# demeter_v21.net
KiCad netlist of a schematic drawn in EAGLE
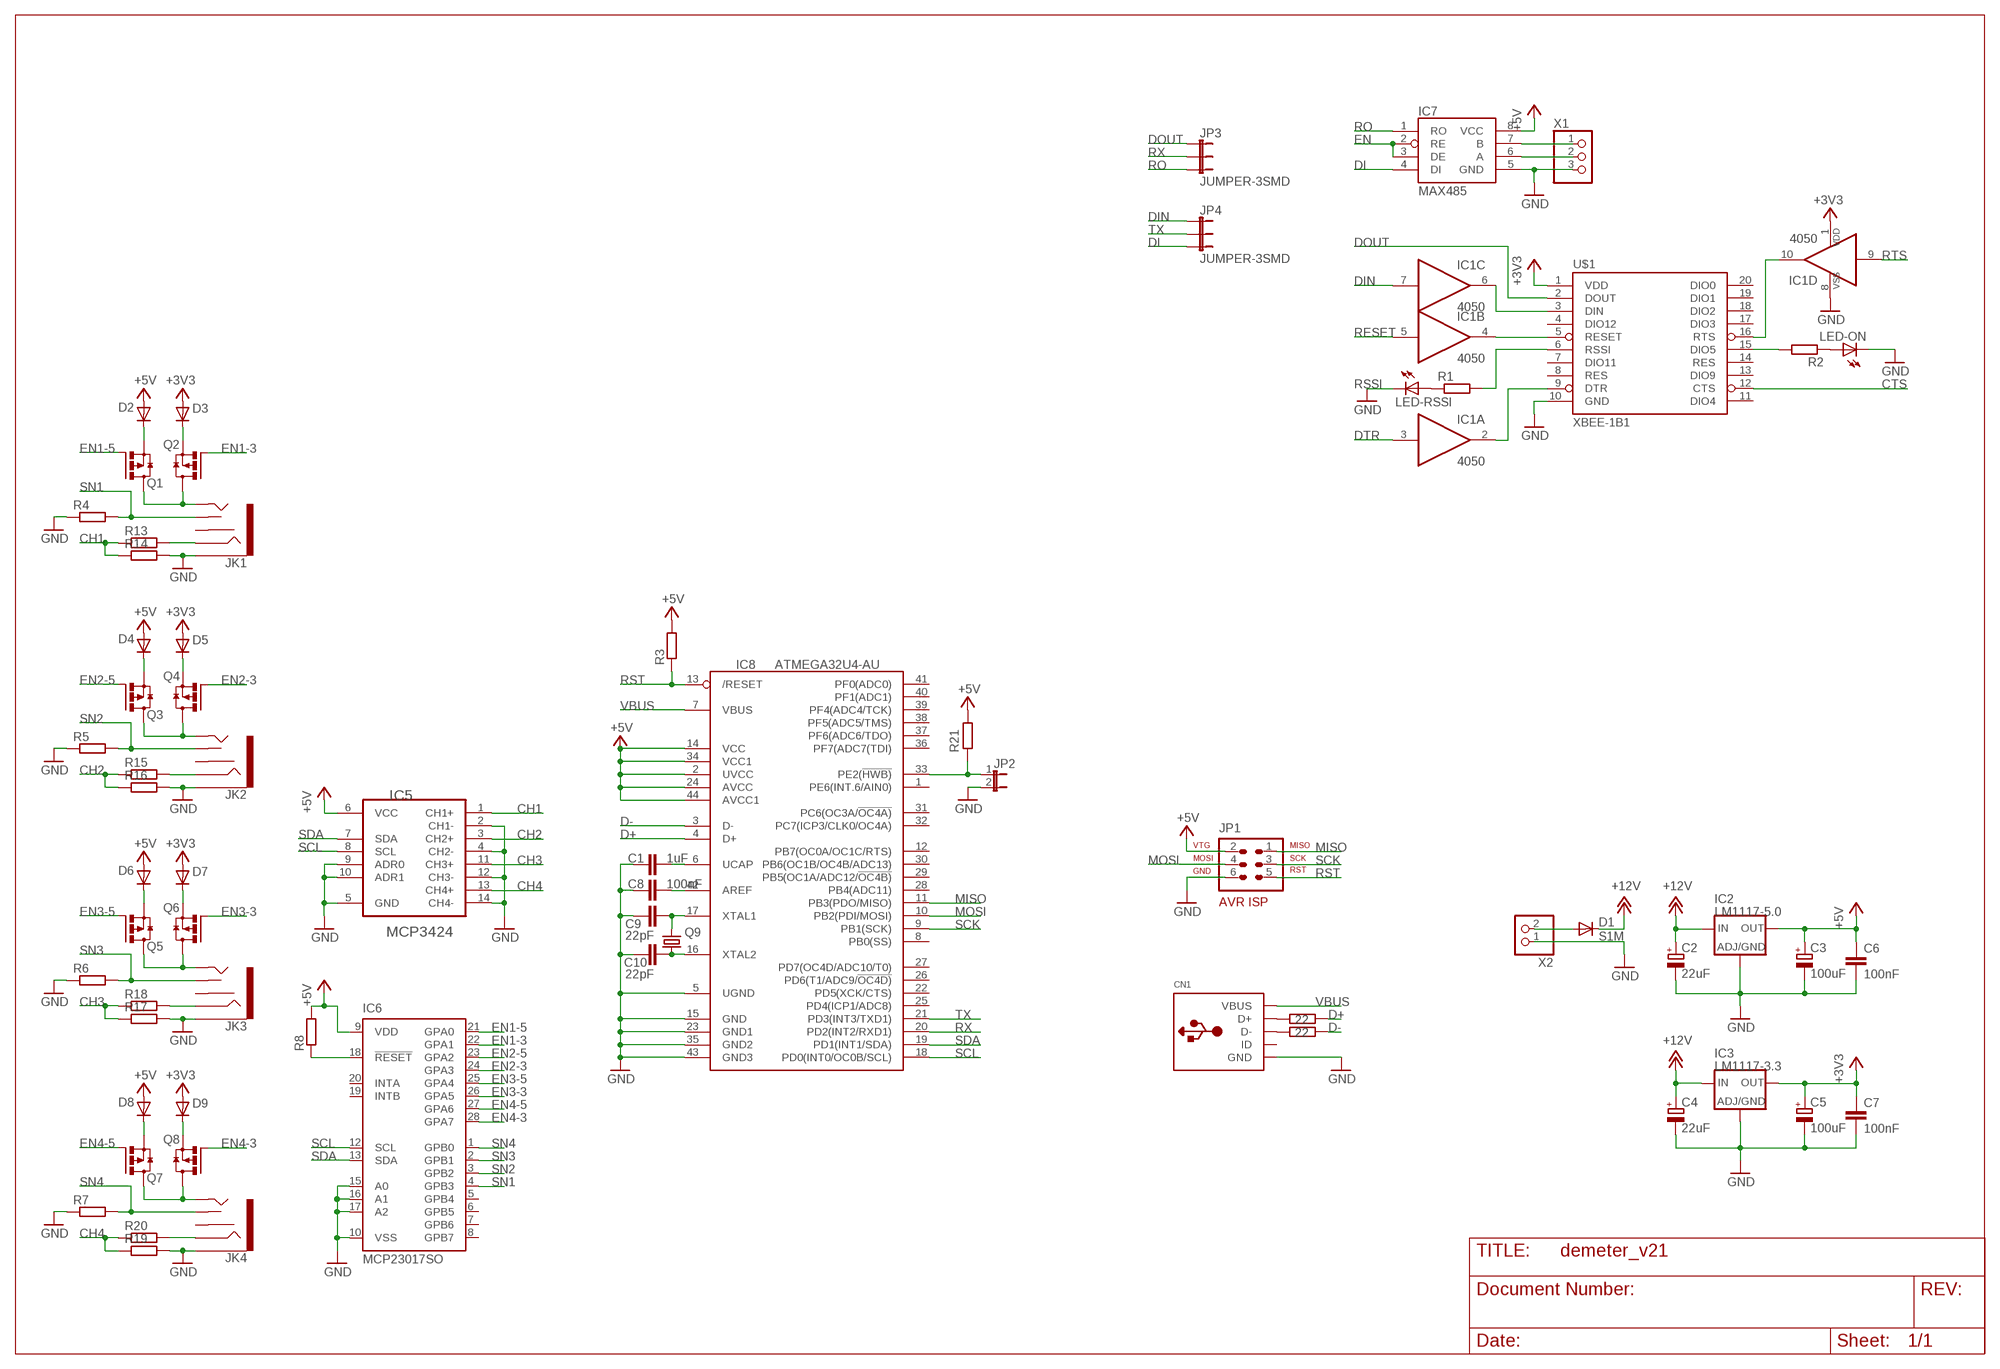
[diagram p0: schematic, sheet 1]

(export (version "E")
  (design (tool "Eeschema 10.0.6"))
  (components
    (comp (ref "C1")
      (value "1uF")
      (footprint "eagle-import:C0805K")
      (libsource (lib "eagle-import") (part "C-EUC0805K"))
    )
    (comp (ref "C2")
      (value "22uF")
      (footprint "eagle-import:PANASONIC_D")
      (libsource (lib "eagle-import") (part "CPOL-EUPD"))
    )
    (comp (ref "C3")
      (value "100uF")
      (footprint "eagle-import:PANASONIC_D")
      (libsource (lib "eagle-import") (part "CPOL-EUPD"))
    )
    (comp (ref "C4")
      (value "22uF")
      (footprint "eagle-import:PANASONIC_D")
      (libsource (lib "eagle-import") (part "CPOL-EUPD"))
    )
    (comp (ref "C5")
      (value "100uF")
      (footprint "eagle-import:PANASONIC_D")
      (libsource (lib "eagle-import") (part "CPOL-EUPD"))
    )
    (comp (ref "C6")
      (value "100nF")
      (footprint "eagle-import:C0805K")
      (libsource (lib "eagle-import") (part "C-EUC0805K"))
    )
    (comp (ref "C7")
      (value "100nF")
      (footprint "eagle-import:C0805K")
      (libsource (lib "eagle-import") (part "C-EUC0805K"))
    )
    (comp (ref "C8")
      (value "100nF")
      (footprint "eagle-import:C0805K")
      (libsource (lib "eagle-import") (part "C-EUC0805K"))
    )
    (comp (ref "C9")
      (value "22pF")
      (footprint "eagle-import:C0805K")
      (libsource (lib "eagle-import") (part "C-EUC0805K"))
    )
    (comp (ref "C10")
      (value "22pF")
      (footprint "eagle-import:C0805K")
      (libsource (lib "eagle-import") (part "C-EUC0805K"))
    )
    (comp (ref "CN1")
      (value "USBMINIB")
      (footprint "eagle-import:USB-MINIB")
      (libsource (lib "eagle-import") (part "USBMINIB"))
    )
    (comp (ref "D1")
      (value "S1M")
      (footprint "eagle-import:DO-214AC")
      (libsource (lib "eagle-import") (part "S1M"))
    )
    (comp (ref "D2")
      (value "MBR0520")
      (footprint "eagle-import:SOD123")
      (libsource (lib "eagle-import") (part "MBR0520"))
    )
    (comp (ref "D3")
      (value "MBR0520")
      (footprint "eagle-import:SOD123")
      (libsource (lib "eagle-import") (part "MBR0520"))
    )
    (comp (ref "D4")
      (value "MBR0520")
      (footprint "eagle-import:SOD123")
      (libsource (lib "eagle-import") (part "MBR0520"))
    )
    (comp (ref "D5")
      (value "MBR0520")
      (footprint "eagle-import:SOD123")
      (libsource (lib "eagle-import") (part "MBR0520"))
    )
    (comp (ref "D6")
      (value "MBR0520")
      (footprint "eagle-import:SOD123")
      (libsource (lib "eagle-import") (part "MBR0520"))
    )
    (comp (ref "D7")
      (value "MBR0520")
      (footprint "eagle-import:SOD123")
      (libsource (lib "eagle-import") (part "MBR0520"))
    )
    (comp (ref "D8")
      (value "MBR0520")
      (footprint "eagle-import:SOD123")
      (libsource (lib "eagle-import") (part "MBR0520"))
    )
    (comp (ref "D9")
      (value "MBR0520")
      (footprint "eagle-import:SOD123")
      (libsource (lib "eagle-import") (part "MBR0520"))
    )
    (comp (ref "IC1")
      (value "4050")
      (footprint "eagle-import:SO16")
      (libsource (lib "eagle-import") (part "4050D"))
    )
    (comp (ref "IC2")
      (value "LM1117-5.0")
      (footprint "eagle-import:DPACK")
      (libsource (lib "eagle-import") (part "LM1117DT"))
    )
    (comp (ref "IC3")
      (value "LM1117-3.3")
      (footprint "eagle-import:DPACK")
      (libsource (lib "eagle-import") (part "LM1117DT"))
    )
    (comp (ref "IC5")
      (value "MCP3424")
      (footprint "eagle-import:SO14")
      (fields (field (name "MPN") "MCP3424-E/SL"))
      (libsource (lib "eagle-import") (part "MCP3424"))
    )
    (comp (ref "IC6")
      (value "MCP23017SO")
      (footprint "eagle-import:SO28W")
      (fields (field (name "MF") "MICROCHIP") (field (name "MPN") "MCP23017-E/SO"))
      (libsource (lib "eagle-import") (part "MCP23017SO"))
    )
    (comp (ref "IC7")
      (value "MAX485")
      (footprint "eagle-import:SO08")
      (libsource (lib "eagle-import") (part "MAX485"))
    )
    (comp (ref "IC8")
      (value "ATMEGA32U4-AU")
      (footprint "eagle-import:TQFP44")
      (libsource (lib "eagle-import") (part "ATMEGA32U4-AU"))
    )
    (comp (ref "JK1")
      (value "AUDIO-JACK2PTH")
      (footprint "eagle-import:AUDIO-JACK")
      (libsource (lib "eagle-import") (part "AUDIO-JACK2PTH"))
    )
    (comp (ref "JK2")
      (value "AUDIO-JACK2PTH")
      (footprint "eagle-import:AUDIO-JACK")
      (libsource (lib "eagle-import") (part "AUDIO-JACK2PTH"))
    )
    (comp (ref "JK3")
      (value "AUDIO-JACK2PTH")
      (footprint "eagle-import:AUDIO-JACK")
      (libsource (lib "eagle-import") (part "AUDIO-JACK2PTH"))
    )
    (comp (ref "JK4")
      (value "AUDIO-JACK2PTH")
      (footprint "eagle-import:AUDIO-JACK")
      (libsource (lib "eagle-import") (part "AUDIO-JACK2PTH"))
    )
    (comp (ref "JP1")
      (value "AVR-ISP-6")
      (footprint "eagle-import:AVR-ISP-6")
      (libsource (lib "eagle-import") (part "AVR-ISP-6"))
    )
    (comp (ref "JP2")
      (value "JUMPER-2SMD-NO")
      (footprint "eagle-import:SJ_2S-NO")
      (libsource (lib "eagle-import") (part "JUMPER-2SMD-NO"))
    )
    (comp (ref "JP3")
      (value "JUMPER-3SMD")
      (footprint "eagle-import:SJ_3")
      (libsource (lib "eagle-import") (part "JUMPER-3SMD"))
    )
    (comp (ref "JP4")
      (value "JUMPER-3SMD")
      (footprint "eagle-import:SJ_3")
      (libsource (lib "eagle-import") (part "JUMPER-3SMD"))
    )
    (comp (ref "LED-ON")
      (value "LED3MM")
      (footprint "eagle-import:LED3MM")
      (libsource (lib "eagle-import") (part "LED3MM"))
    )
    (comp (ref "LED-RSSI")
      (value "LED3MM")
      (footprint "eagle-import:LED3MM")
      (libsource (lib "eagle-import") (part "LED3MM"))
    )
    (comp (ref "Q1")
      (value "IRLML6402")
      (footprint "eagle-import:SOT23")
      (libsource (lib "eagle-import") (part "IRLML6402"))
    )
    (comp (ref "Q2")
      (value "IRLML6402")
      (footprint "eagle-import:SOT23")
      (libsource (lib "eagle-import") (part "IRLML6402"))
    )
    (comp (ref "Q3")
      (value "IRLML6402")
      (footprint "eagle-import:SOT23")
      (libsource (lib "eagle-import") (part "IRLML6402"))
    )
    (comp (ref "Q4")
      (value "IRLML6402")
      (footprint "eagle-import:SOT23")
      (libsource (lib "eagle-import") (part "IRLML6402"))
    )
    (comp (ref "Q5")
      (value "IRLML6402")
      (footprint "eagle-import:SOT23")
      (libsource (lib "eagle-import") (part "IRLML6402"))
    )
    (comp (ref "Q6")
      (value "IRLML6402")
      (footprint "eagle-import:SOT23")
      (libsource (lib "eagle-import") (part "IRLML6402"))
    )
    (comp (ref "Q7")
      (value "IRLML6402")
      (footprint "eagle-import:SOT23")
      (libsource (lib "eagle-import") (part "IRLML6402"))
    )
    (comp (ref "Q8")
      (value "IRLML6402")
      (footprint "eagle-import:SOT23")
      (libsource (lib "eagle-import") (part "IRLML6402"))
    )
    (comp (ref "Q9")
      (value "CRYSTALHC49UP")
      (footprint "eagle-import:HC49UP")
      (libsource (lib "eagle-import") (part "CRYSTALHC49UP"))
    )
    (comp (ref "R1")
      (value "R-EU_R0805")
      (footprint "eagle-import:R0805")
      (libsource (lib "eagle-import") (part "R-EU_R0805"))
    )
    (comp (ref "R2")
      (value "R-EU_R0805")
      (footprint "eagle-import:R0805")
      (libsource (lib "eagle-import") (part "R-EU_R0805"))
    )
    (comp (ref "R3")
      (value "R-EU_R0805")
      (footprint "eagle-import:R0805")
      (libsource (lib "eagle-import") (part "R-EU_R0805"))
    )
    (comp (ref "R4")
      (value "R-EU_R0805")
      (footprint "eagle-import:R0805")
      (libsource (lib "eagle-import") (part "R-EU_R0805"))
    )
    (comp (ref "R5")
      (value "R-EU_R0805")
      (footprint "eagle-import:R0805")
      (libsource (lib "eagle-import") (part "R-EU_R0805"))
    )
    (comp (ref "R6")
      (value "R-EU_R0805")
      (footprint "eagle-import:R0805")
      (libsource (lib "eagle-import") (part "R-EU_R0805"))
    )
    (comp (ref "R7")
      (value "R-EU_R0805")
      (footprint "eagle-import:R0805")
      (libsource (lib "eagle-import") (part "R-EU_R0805"))
    )
    (comp (ref "R8")
      (value "R-EU_R0805")
      (footprint "eagle-import:R0805")
      (libsource (lib "eagle-import") (part "R-EU_R0805"))
    )
    (comp (ref "R9")
      (value "22")
      (footprint "eagle-import:R0805")
      (libsource (lib "eagle-import") (part "R-EU_R0805"))
    )
    (comp (ref "R10")
      (value "22")
      (footprint "eagle-import:R0805")
      (libsource (lib "eagle-import") (part "R-EU_R0805"))
    )
    (comp (ref "R13")
      (value "R-EU_R0805")
      (footprint "eagle-import:R0805")
      (libsource (lib "eagle-import") (part "R-EU_R0805"))
    )
    (comp (ref "R14")
      (value "R-EU_R0805")
      (footprint "eagle-import:R0805")
      (libsource (lib "eagle-import") (part "R-EU_R0805"))
    )
    (comp (ref "R15")
      (value "R-EU_R0805")
      (footprint "eagle-import:R0805")
      (libsource (lib "eagle-import") (part "R-EU_R0805"))
    )
    (comp (ref "R16")
      (value "R-EU_R0805")
      (footprint "eagle-import:R0805")
      (libsource (lib "eagle-import") (part "R-EU_R0805"))
    )
    (comp (ref "R17")
      (value "R-EU_R0805")
      (footprint "eagle-import:R0805")
      (libsource (lib "eagle-import") (part "R-EU_R0805"))
    )
    (comp (ref "R18")
      (value "R-EU_R0805")
      (footprint "eagle-import:R0805")
      (libsource (lib "eagle-import") (part "R-EU_R0805"))
    )
    (comp (ref "R19")
      (value "R-EU_R0805")
      (footprint "eagle-import:R0805")
      (libsource (lib "eagle-import") (part "R-EU_R0805"))
    )
    (comp (ref "R20")
      (value "R-EU_R0805")
      (footprint "eagle-import:R0805")
      (libsource (lib "eagle-import") (part "R-EU_R0805"))
    )
    (comp (ref "R21")
      (value "R-EU_R0805")
      (footprint "eagle-import:R0805")
      (libsource (lib "eagle-import") (part "R-EU_R0805"))
    )
    (comp (ref "U$1")
      (value "XBEE-1B1")
      (footprint "eagle-import:XBEE-1")
      (libsource (lib "eagle-import") (part "XBEE-1B1"))
    )
    (comp (ref "X1")
      (value "W237-103")
      (footprint "eagle-import:W237-103")
      (libsource (lib "eagle-import") (part "W237-103"))
    )
    (comp (ref "X2")
      (value "W237-102")
      (footprint "eagle-import:W237-102")
      (libsource (lib "eagle-import") (part "W237-102"))
    )
  )
  (nets
    (net (code "1") (name "+3V3") (class "Default")
      (node (ref "C5") (pin "+") (pinfunction "+_+") (pintype "passive"))
      (node (ref "C7") (pin "1") (pinfunction "1_1") (pintype "passive"))
      (node (ref "D3") (pin "A") (pinfunction "A_A") (pintype "passive"))
      (node (ref "D5") (pin "A") (pinfunction "A_A") (pintype "passive"))
      (node (ref "D7") (pin "A") (pinfunction "A_A") (pintype "passive"))
      (node (ref "D9") (pin "A") (pinfunction "A_A") (pintype "passive"))
      (node (ref "IC1") (pin "1") (pinfunction "VDD_1") (pintype "power_in"))
      (node (ref "IC3") (pin "4") (pinfunction "OUT_4") (pintype "passive"))
      (node (ref "U$1") (pin "1") (pinfunction "VDD_1") (pintype "power_in"))
    )
    (net (code "2") (name "+5V") (class "Default")
      (node (ref "C3") (pin "+") (pinfunction "+_+") (pintype "passive"))
      (node (ref "C6") (pin "1") (pinfunction "1_1") (pintype "passive"))
      (node (ref "D2") (pin "A") (pinfunction "A_A") (pintype "passive"))
      (node (ref "D4") (pin "A") (pinfunction "A_A") (pintype "passive"))
      (node (ref "D6") (pin "A") (pinfunction "A_A") (pintype "passive"))
      (node (ref "D8") (pin "A") (pinfunction "A_A") (pintype "passive"))
      (node (ref "IC2") (pin "4") (pinfunction "OUT_4") (pintype "passive"))
      (node (ref "IC5") (pin "6") (pinfunction "VCC_6") (pintype "power_in"))
      (node (ref "IC6") (pin "9") (pinfunction "VDD_9") (pintype "power_in"))
      (node (ref "IC7") (pin "8") (pinfunction "VCC_8") (pintype "bidirectional"))
      (node (ref "IC8") (pin "14") (pinfunction "VCC_14") (pintype "bidirectional"))
      (node (ref "IC8") (pin "2") (pinfunction "UVCC_2") (pintype "bidirectional"))
      (node (ref "IC8") (pin "24") (pinfunction "AVCC_24") (pintype "bidirectional"))
      (node (ref "IC8") (pin "34") (pinfunction "VCC1_34") (pintype "bidirectional"))
      (node (ref "IC8") (pin "44") (pinfunction "AVCC1_44") (pintype "bidirectional"))
      (node (ref "JP1") (pin "2") (pinfunction "VTG_2") (pintype "passive"))
      (node (ref "R21") (pin "1") (pinfunction "1_1") (pintype "passive"))
      (node (ref "R3") (pin "2") (pinfunction "2_2") (pintype "passive"))
      (node (ref "R8") (pin "2") (pinfunction "2_2") (pintype "passive"))
    )
    (net (code "3") (name "+12V") (class "Default")
      (node (ref "C2") (pin "+") (pinfunction "+_+") (pintype "passive"))
      (node (ref "C4") (pin "+") (pinfunction "+_+") (pintype "passive"))
      (node (ref "D1") (pin "C") (pinfunction "C_C") (pintype "passive"))
      (node (ref "IC2") (pin "3") (pinfunction "IN_3") (pintype "input"))
      (node (ref "IC3") (pin "3") (pinfunction "IN_3") (pintype "input"))
    )
    (net (code "4") (name "/CH1") (class "Default")
      (node (ref "IC5") (pin "1") (pinfunction "CH1+_1") (pintype "input"))
      (node (ref "R13") (pin "1") (pinfunction "1_1") (pintype "passive"))
      (node (ref "R14") (pin "1") (pinfunction "1_1") (pintype "passive"))
    )
    (net (code "5") (name "/CH2") (class "Default")
      (node (ref "IC5") (pin "3") (pinfunction "CH2+_3") (pintype "input"))
      (node (ref "R15") (pin "1") (pinfunction "1_1") (pintype "passive"))
      (node (ref "R16") (pin "1") (pinfunction "1_1") (pintype "passive"))
    )
    (net (code "6") (name "/CH3") (class "Default")
      (node (ref "IC5") (pin "11") (pinfunction "CH3+_11") (pintype "input"))
      (node (ref "R17") (pin "1") (pinfunction "1_1") (pintype "passive"))
      (node (ref "R18") (pin "1") (pinfunction "1_1") (pintype "passive"))
    )
    (net (code "7") (name "/CH4") (class "Default")
      (node (ref "IC5") (pin "13") (pinfunction "CH4+_13") (pintype "input"))
      (node (ref "R19") (pin "1") (pinfunction "1_1") (pintype "passive"))
      (node (ref "R20") (pin "1") (pinfunction "1_1") (pintype "passive"))
    )
    (net (code "8") (name "/CTS") (class "Default")
      (node (ref "U$1") (pin "12") (pinfunction "CTS_12") (pintype "output"))
    )
    (net (code "9") (name "/D+") (class "Default")
      (node (ref "IC8") (pin "4") (pinfunction "D+_4") (pintype "bidirectional"))
      (node (ref "R9") (pin "1") (pinfunction "1_1") (pintype "passive"))
    )
    (net (code "10") (name "/D-") (class "Default")
      (node (ref "IC8") (pin "3") (pinfunction "D-_3") (pintype "bidirectional"))
      (node (ref "R10") (pin "1") (pinfunction "1_1") (pintype "passive"))
    )
    (net (code "11") (name "/DI") (class "Default")
      (node (ref "IC7") (pin "4") (pinfunction "DI_4") (pintype "bidirectional"))
      (node (ref "JP4") (pin "3") (pinfunction "3_3") (pintype "passive"))
    )
    (net (code "12") (name "/DIN") (class "Default")
      (node (ref "IC1") (pin "7") (pinfunction "I_7") (pintype "input"))
      (node (ref "JP4") (pin "1") (pinfunction "1_1") (pintype "passive"))
    )
    (net (code "13") (name "/DOUT") (class "Default")
      (node (ref "JP3") (pin "1") (pinfunction "1_1") (pintype "passive"))
      (node (ref "U$1") (pin "2") (pinfunction "DOUT_2") (pintype "output"))
    )
    (net (code "14") (name "/DTR") (class "Default")
      (node (ref "IC1") (pin "3") (pinfunction "I_3") (pintype "input"))
    )
    (net (code "15") (name "/EN") (class "Default")
      (node (ref "IC7") (pin "2") (pinfunction "RE_2") (pintype "bidirectional"))
      (node (ref "IC7") (pin "3") (pinfunction "DE_3") (pintype "bidirectional"))
    )
    (net (code "16") (name "/EN1-3") (class "Default")
      (node (ref "IC6") (pin "22") (pinfunction "GPA1_22") (pintype "bidirectional"))
      (node (ref "Q2") (pin "1") (pinfunction "G_1") (pintype "passive"))
    )
    (net (code "17") (name "/EN1-5") (class "Default")
      (node (ref "IC6") (pin "21") (pinfunction "GPA0_21") (pintype "bidirectional"))
      (node (ref "Q1") (pin "1") (pinfunction "G_1") (pintype "passive"))
    )
    (net (code "18") (name "/EN2-3") (class "Default")
      (node (ref "IC6") (pin "24") (pinfunction "GPA3_24") (pintype "bidirectional"))
      (node (ref "Q4") (pin "1") (pinfunction "G_1") (pintype "passive"))
    )
    (net (code "19") (name "/EN2-5") (class "Default")
      (node (ref "IC6") (pin "23") (pinfunction "GPA2_23") (pintype "bidirectional"))
      (node (ref "Q3") (pin "1") (pinfunction "G_1") (pintype "passive"))
    )
    (net (code "20") (name "/EN3-3") (class "Default")
      (node (ref "IC6") (pin "26") (pinfunction "GPA5_26") (pintype "bidirectional"))
      (node (ref "Q6") (pin "1") (pinfunction "G_1") (pintype "passive"))
    )
    (net (code "21") (name "/EN3-5") (class "Default")
      (node (ref "IC6") (pin "25") (pinfunction "GPA4_25") (pintype "bidirectional"))
      (node (ref "Q5") (pin "1") (pinfunction "G_1") (pintype "passive"))
    )
    (net (code "22") (name "/EN4-3") (class "Default")
      (node (ref "IC6") (pin "28") (pinfunction "GPA7_28") (pintype "bidirectional"))
      (node (ref "Q8") (pin "1") (pinfunction "G_1") (pintype "passive"))
    )
    (net (code "23") (name "/EN4-5") (class "Default")
      (node (ref "IC6") (pin "27") (pinfunction "GPA6_27") (pintype "bidirectional"))
      (node (ref "Q7") (pin "1") (pinfunction "G_1") (pintype "passive"))
    )
    (net (code "24") (name "/MISO") (class "Default")
      (node (ref "IC8") (pin "11") (pinfunction "PB3(PDO/MISO)_11") (pintype "bidirectional"))
      (node (ref "JP1") (pin "1") (pinfunction "MISO_1") (pintype "passive"))
    )
    (net (code "25") (name "/MOSI") (class "Default")
      (node (ref "IC8") (pin "10") (pinfunction "PB2(PDI/MOSI)_10") (pintype "bidirectional"))
      (node (ref "JP1") (pin "4") (pinfunction "MOSI_4") (pintype "passive"))
    )
    (net (code "26") (name "/RESET") (class "Default")
      (node (ref "IC1") (pin "5") (pinfunction "I_5") (pintype "input"))
    )
    (net (code "27") (name "/RO") (class "Default")
      (node (ref "IC7") (pin "1") (pinfunction "RO_1") (pintype "bidirectional"))
      (node (ref "JP3") (pin "3") (pinfunction "3_3") (pintype "passive"))
    )
    (net (code "28") (name "/RSSI") (class "Default")
      (node (ref "R1") (pin "2") (pinfunction "2_2") (pintype "passive"))
      (node (ref "U$1") (pin "6") (pinfunction "RSSI_6") (pintype "bidirectional"))
    )
    (net (code "29") (name "/RST") (class "Default")
      (node (ref "IC8") (pin "13") (pinfunction "/RESET_13") (pintype "bidirectional"))
      (node (ref "JP1") (pin "5") (pinfunction "RST_5") (pintype "passive"))
      (node (ref "R3") (pin "1") (pinfunction "1_1") (pintype "passive"))
    )
    (net (code "30") (name "/RTS") (class "Default")
      (node (ref "IC1") (pin "9") (pinfunction "I_9") (pintype "input"))
    )
    (net (code "31") (name "/RX") (class "Default")
      (node (ref "IC8") (pin "20") (pinfunction "PD2(INT2/RXD1)_20") (pintype "bidirectional"))
      (node (ref "JP3") (pin "2") (pinfunction "2_2") (pintype "passive"))
    )
    (net (code "32") (name "/SCK") (class "Default")
      (node (ref "IC8") (pin "9") (pinfunction "PB1(SCK)_9") (pintype "bidirectional"))
      (node (ref "JP1") (pin "3") (pinfunction "SCK_3") (pintype "passive"))
    )
    (net (code "33") (name "/SCL") (class "Default")
      (node (ref "IC5") (pin "8") (pinfunction "SCL_8") (pintype "input"))
      (node (ref "IC6") (pin "12") (pinfunction "SCL_12") (pintype "input"))
      (node (ref "IC8") (pin "18") (pinfunction "PD0(INT0/OC0B/SCL)_18") (pintype "bidirectional"))
    )
    (net (code "34") (name "/SDA") (class "Default")
      (node (ref "IC5") (pin "7") (pinfunction "SDA_7") (pintype "bidirectional"))
      (node (ref "IC6") (pin "13") (pinfunction "SDA_13") (pintype "bidirectional"))
      (node (ref "IC8") (pin "19") (pinfunction "PD1(INT1/SDA)_19") (pintype "bidirectional"))
    )
    (net (code "35") (name "/SN1") (class "Default")
      (node (ref "IC6") (pin "4") (pinfunction "GPB3_4") (pintype "bidirectional"))
      (node (ref "JK1") (pin "TSH") (pinfunction "TSH_TSH") (pintype "bidirectional"))
      (node (ref "R4") (pin "2") (pinfunction "2_2") (pintype "passive"))
    )
    (net (code "36") (name "/SN2") (class "Default")
      (node (ref "IC6") (pin "3") (pinfunction "GPB2_3") (pintype "bidirectional"))
      (node (ref "JK2") (pin "TSH") (pinfunction "TSH_TSH") (pintype "bidirectional"))
      (node (ref "R5") (pin "2") (pinfunction "2_2") (pintype "passive"))
    )
    (net (code "37") (name "/SN3") (class "Default")
      (node (ref "IC6") (pin "2") (pinfunction "GPB1_2") (pintype "bidirectional"))
      (node (ref "JK3") (pin "TSH") (pinfunction "TSH_TSH") (pintype "bidirectional"))
      (node (ref "R6") (pin "2") (pinfunction "2_2") (pintype "passive"))
    )
    (net (code "38") (name "/SN4") (class "Default")
      (node (ref "IC6") (pin "1") (pinfunction "GPB0_1") (pintype "bidirectional"))
      (node (ref "JK4") (pin "TSH") (pinfunction "TSH_TSH") (pintype "bidirectional"))
      (node (ref "R7") (pin "2") (pinfunction "2_2") (pintype "passive"))
    )
    (net (code "39") (name "/TX") (class "Default")
      (node (ref "IC8") (pin "21") (pinfunction "PD3(INT3/TXD1)_21") (pintype "bidirectional"))
      (node (ref "JP4") (pin "2") (pinfunction "2_2") (pintype "passive"))
    )
    (net (code "40") (name "/VBUS") (class "Default")
      (node (ref "CN1") (pin "VBUS") (pinfunction "VBUS_VBUS") (pintype "power_in"))
      (node (ref "IC8") (pin "7") (pinfunction "VBUS_7") (pintype "bidirectional"))
    )
    (net (code "41") (name "GND") (class "Default")
      (node (ref "C1") (pin "2") (pinfunction "2_2") (pintype "passive"))
      (node (ref "C10") (pin "2") (pinfunction "2_2") (pintype "passive"))
      (node (ref "C2") (pin "-") (pinfunction "-_-") (pintype "passive"))
      (node (ref "C3") (pin "-") (pinfunction "-_-") (pintype "passive"))
      (node (ref "C4") (pin "-") (pinfunction "-_-") (pintype "passive"))
      (node (ref "C5") (pin "-") (pinfunction "-_-") (pintype "passive"))
      (node (ref "C6") (pin "2") (pinfunction "2_2") (pintype "passive"))
      (node (ref "C7") (pin "2") (pinfunction "2_2") (pintype "passive"))
      (node (ref "C8") (pin "2") (pinfunction "2_2") (pintype "passive"))
      (node (ref "C9") (pin "2") (pinfunction "2_2") (pintype "passive"))
      (node (ref "CN1") (pin "GND") (pinfunction "GND_GND") (pintype "power_in"))
      (node (ref "IC1") (pin "8") (pinfunction "VSS_8") (pintype "power_in"))
      (node (ref "IC2") (pin "1") (pinfunction "ADJ_1") (pintype "input"))
      (node (ref "IC3") (pin "1") (pinfunction "ADJ_1") (pintype "input"))
      (node (ref "IC5") (pin "10") (pinfunction "ADR1_10") (pintype "input"))
      (node (ref "IC5") (pin "12") (pinfunction "CH3-_12") (pintype "input"))
      (node (ref "IC5") (pin "14") (pinfunction "CH4-_14") (pintype "input"))
      (node (ref "IC5") (pin "2") (pinfunction "CH1-_2") (pintype "input"))
      (node (ref "IC5") (pin "4") (pinfunction "CH2-_4") (pintype "input"))
      (node (ref "IC5") (pin "5") (pinfunction "GND_5") (pintype "power_in"))
      (node (ref "IC5") (pin "9") (pinfunction "ADR0_9") (pintype "input"))
      (node (ref "IC6") (pin "10") (pinfunction "VSS_10") (pintype "power_in"))
      (node (ref "IC6") (pin "15") (pinfunction "A0_15") (pintype "input"))
      (node (ref "IC6") (pin "16") (pinfunction "A1_16") (pintype "input"))
      (node (ref "IC6") (pin "17") (pinfunction "A2_17") (pintype "input"))
      (node (ref "IC7") (pin "5") (pinfunction "GND_5") (pintype "bidirectional"))
      (node (ref "IC8") (pin "15") (pinfunction "GND_15") (pintype "bidirectional"))
      (node (ref "IC8") (pin "23") (pinfunction "GND1_23") (pintype "bidirectional"))
      (node (ref "IC8") (pin "35") (pinfunction "GND2_35") (pintype "bidirectional"))
      (node (ref "IC8") (pin "43") (pinfunction "GND3_43") (pintype "bidirectional"))
      (node (ref "IC8") (pin "5") (pinfunction "UGND_5") (pintype "bidirectional"))
      (node (ref "JK1") (pin "SLEEVE") (pinfunction "SLEEVE_SLEEVE") (pintype "bidirectional"))
      (node (ref "JK2") (pin "SLEEVE") (pinfunction "SLEEVE_SLEEVE") (pintype "bidirectional"))
      (node (ref "JK3") (pin "SLEEVE") (pinfunction "SLEEVE_SLEEVE") (pintype "bidirectional"))
      (node (ref "JK4") (pin "SLEEVE") (pinfunction "SLEEVE_SLEEVE") (pintype "bidirectional"))
      (node (ref "JP1") (pin "6") (pinfunction "GND_6") (pintype "passive"))
      (node (ref "JP2") (pin "2") (pinfunction "2_2") (pintype "passive"))
      (node (ref "LED-ON") (pin "K") (pinfunction "C_K") (pintype "passive"))
      (node (ref "LED-RSSI") (pin "K") (pinfunction "C_K") (pintype "passive"))
      (node (ref "R14") (pin "2") (pinfunction "2_2") (pintype "passive"))
      (node (ref "R16") (pin "2") (pinfunction "2_2") (pintype "passive"))
      (node (ref "R17") (pin "2") (pinfunction "2_2") (pintype "passive"))
      (node (ref "R19") (pin "2") (pinfunction "2_2") (pintype "passive"))
      (node (ref "R4") (pin "1") (pinfunction "1_1") (pintype "passive"))
      (node (ref "R5") (pin "1") (pinfunction "1_1") (pintype "passive"))
      (node (ref "R6") (pin "1") (pinfunction "1_1") (pintype "passive"))
      (node (ref "R7") (pin "1") (pinfunction "1_1") (pintype "passive"))
      (node (ref "U$1") (pin "10") (pinfunction "GND_10") (pintype "power_in"))
      (node (ref "X1") (pin "3") (pinfunction "3_3") (pintype "passive"))
      (node (ref "X2") (pin "1") (pinfunction "1_1") (pintype "passive"))
    )
    (net (code "42") (name "Net-(CN1-PadD+)") (class "Default")
      (node (ref "CN1") (pin "D+") (pinfunction "D+_D+") (pintype "bidirectional"))
      (node (ref "R9") (pin "2") (pinfunction "2_2") (pintype "passive"))
    )
    (net (code "43") (name "Net-(CN1-PadD-)") (class "Default")
      (node (ref "CN1") (pin "D-") (pinfunction "D-_D-") (pintype "bidirectional"))
      (node (ref "R10") (pin "2") (pinfunction "2_2") (pintype "passive"))
    )
    (net (code "44") (name "Net-(D1-PadA)") (class "Default")
      (node (ref "D1") (pin "A") (pinfunction "A_A") (pintype "passive"))
      (node (ref "X2") (pin "2") (pinfunction "2_2") (pintype "passive"))
    )
    (net (code "45") (name "Net-(IC1A-O)") (class "Default")
      (node (ref "IC1") (pin "2") (pinfunction "O_2") (pintype "output"))
      (node (ref "U$1") (pin "9") (pinfunction "DTR_9") (pintype "bidirectional"))
    )
    (net (code "46") (name "Net-(IC1B-O)") (class "Default")
      (node (ref "IC1") (pin "4") (pinfunction "O_4") (pintype "output"))
      (node (ref "U$1") (pin "5") (pinfunction "RESET_5") (pintype "input"))
    )
    (net (code "47") (name "Net-(IC1C-O)") (class "Default")
      (node (ref "IC1") (pin "6") (pinfunction "O_6") (pintype "output"))
      (node (ref "U$1") (pin "3") (pinfunction "DIN_3") (pintype "input"))
    )
    (net (code "48") (name "Net-(IC1D-O)") (class "Default")
      (node (ref "IC1") (pin "10") (pinfunction "O_10") (pintype "output"))
      (node (ref "U$1") (pin "16") (pinfunction "RTS_16") (pintype "input"))
    )
    (net (code "49") (name "Net-(IC6-~{RESET})") (class "Default")
      (node (ref "IC6") (pin "18") (pinfunction "~{RESET}_18") (pintype "input"))
      (node (ref "R8") (pin "1") (pinfunction "1_1") (pintype "passive"))
    )
    (net (code "50") (name "Net-(IC7-A)") (class "Default")
      (node (ref "IC7") (pin "6") (pinfunction "A_6") (pintype "bidirectional"))
      (node (ref "X1") (pin "2") (pinfunction "2_2") (pintype "passive"))
    )
    (net (code "51") (name "Net-(IC7-B)") (class "Default")
      (node (ref "IC7") (pin "7") (pinfunction "B_7") (pintype "bidirectional"))
      (node (ref "X1") (pin "1") (pinfunction "1_1") (pintype "passive"))
    )
    (net (code "52") (name "Net-(IC8-AREF)") (class "Default")
      (node (ref "C8") (pin "1") (pinfunction "1_1") (pintype "passive"))
      (node (ref "IC8") (pin "42") (pinfunction "AREF_42") (pintype "bidirectional"))
    )
    (net (code "53") (name "Net-(IC8-PE2(~{HWB}))") (class "Default")
      (node (ref "IC8") (pin "33") (pinfunction "PE2(~{HWB})_33") (pintype "bidirectional"))
      (node (ref "JP2") (pin "1") (pinfunction "1_1") (pintype "passive"))
      (node (ref "R21") (pin "2") (pinfunction "2_2") (pintype "passive"))
    )
    (net (code "54") (name "Net-(IC8-UCAP)") (class "Default")
      (node (ref "C1") (pin "1") (pinfunction "1_1") (pintype "passive"))
      (node (ref "IC8") (pin "6") (pinfunction "UCAP_6") (pintype "bidirectional"))
    )
    (net (code "55") (name "Net-(IC8-XTAL1)") (class "Default")
      (node (ref "C9") (pin "1") (pinfunction "1_1") (pintype "passive"))
      (node (ref "IC8") (pin "17") (pinfunction "XTAL1_17") (pintype "bidirectional"))
      (node (ref "Q9") (pin "2") (pinfunction "2_2") (pintype "passive"))
    )
    (net (code "56") (name "Net-(IC8-XTAL2)") (class "Default")
      (node (ref "C10") (pin "1") (pinfunction "1_1") (pintype "passive"))
      (node (ref "IC8") (pin "16") (pinfunction "XTAL2_16") (pintype "bidirectional"))
      (node (ref "Q9") (pin "1") (pinfunction "1_1") (pintype "passive"))
    )
    (net (code "57") (name "Net-(JK1-PadRING)") (class "Default")
      (node (ref "JK1") (pin "RING") (pinfunction "RING_RING") (pintype "bidirectional"))
      (node (ref "R13") (pin "2") (pinfunction "2_2") (pintype "passive"))
    )
    (net (code "58") (name "Net-(JK2-PadRING)") (class "Default")
      (node (ref "JK2") (pin "RING") (pinfunction "RING_RING") (pintype "bidirectional"))
      (node (ref "R15") (pin "2") (pinfunction "2_2") (pintype "passive"))
    )
    (net (code "59") (name "Net-(JK3-PadRING)") (class "Default")
      (node (ref "JK3") (pin "RING") (pinfunction "RING_RING") (pintype "bidirectional"))
      (node (ref "R18") (pin "2") (pinfunction "2_2") (pintype "passive"))
    )
    (net (code "60") (name "Net-(JK4-PadRING)") (class "Default")
      (node (ref "JK4") (pin "RING") (pinfunction "RING_RING") (pintype "bidirectional"))
      (node (ref "R20") (pin "2") (pinfunction "2_2") (pintype "passive"))
    )
    (net (code "61") (name "Net-(LED-ON-PadA)") (class "Default")
      (node (ref "LED-ON") (pin "A") (pinfunction "A_A") (pintype "passive"))
      (node (ref "R2") (pin "1") (pinfunction "1_1") (pintype "passive"))
    )
    (net (code "62") (name "Net-(LED-RSSI-PadA)") (class "Default")
      (node (ref "LED-RSSI") (pin "A") (pinfunction "A_A") (pintype "passive"))
      (node (ref "R1") (pin "1") (pinfunction "1_1") (pintype "passive"))
    )
    (net (code "63") (name "Net-(Q1-D)") (class "Default")
      (node (ref "JK1") (pin "TIP") (pinfunction "TIP_TIP") (pintype "bidirectional"))
      (node (ref "Q1") (pin "3") (pinfunction "D_3") (pintype "passive"))
      (node (ref "Q2") (pin "3") (pinfunction "D_3") (pintype "passive"))
    )
    (net (code "64") (name "Net-(Q1-S)") (class "Default")
      (node (ref "D2") (pin "C") (pinfunction "C_C") (pintype "passive"))
      (node (ref "Q1") (pin "2") (pinfunction "S_2") (pintype "passive"))
    )
    (net (code "65") (name "Net-(Q2-S)") (class "Default")
      (node (ref "D3") (pin "C") (pinfunction "C_C") (pintype "passive"))
      (node (ref "Q2") (pin "2") (pinfunction "S_2") (pintype "passive"))
    )
    (net (code "66") (name "Net-(Q3-D)") (class "Default")
      (node (ref "JK2") (pin "TIP") (pinfunction "TIP_TIP") (pintype "bidirectional"))
      (node (ref "Q3") (pin "3") (pinfunction "D_3") (pintype "passive"))
      (node (ref "Q4") (pin "3") (pinfunction "D_3") (pintype "passive"))
    )
    (net (code "67") (name "Net-(Q3-S)") (class "Default")
      (node (ref "D4") (pin "C") (pinfunction "C_C") (pintype "passive"))
      (node (ref "Q3") (pin "2") (pinfunction "S_2") (pintype "passive"))
    )
    (net (code "68") (name "Net-(Q4-S)") (class "Default")
      (node (ref "D5") (pin "C") (pinfunction "C_C") (pintype "passive"))
      (node (ref "Q4") (pin "2") (pinfunction "S_2") (pintype "passive"))
    )
    (net (code "69") (name "Net-(Q5-D)") (class "Default")
      (node (ref "JK3") (pin "TIP") (pinfunction "TIP_TIP") (pintype "bidirectional"))
      (node (ref "Q5") (pin "3") (pinfunction "D_3") (pintype "passive"))
      (node (ref "Q6") (pin "3") (pinfunction "D_3") (pintype "passive"))
    )
    (net (code "70") (name "Net-(Q5-S)") (class "Default")
      (node (ref "D6") (pin "C") (pinfunction "C_C") (pintype "passive"))
      (node (ref "Q5") (pin "2") (pinfunction "S_2") (pintype "passive"))
    )
    (net (code "71") (name "Net-(Q6-S)") (class "Default")
      (node (ref "D7") (pin "C") (pinfunction "C_C") (pintype "passive"))
      (node (ref "Q6") (pin "2") (pinfunction "S_2") (pintype "passive"))
    )
    (net (code "72") (name "Net-(Q7-D)") (class "Default")
      (node (ref "JK4") (pin "TIP") (pinfunction "TIP_TIP") (pintype "bidirectional"))
      (node (ref "Q7") (pin "3") (pinfunction "D_3") (pintype "passive"))
      (node (ref "Q8") (pin "3") (pinfunction "D_3") (pintype "passive"))
    )
    (net (code "73") (name "Net-(Q7-S)") (class "Default")
      (node (ref "D8") (pin "C") (pinfunction "C_C") (pintype "passive"))
      (node (ref "Q7") (pin "2") (pinfunction "S_2") (pintype "passive"))
    )
    (net (code "74") (name "Net-(Q8-S)") (class "Default")
      (node (ref "D9") (pin "C") (pinfunction "C_C") (pintype "passive"))
      (node (ref "Q8") (pin "2") (pinfunction "S_2") (pintype "passive"))
    )
    (net (code "75") (name "Net-(U$1-DIO5)") (class "Default")
      (node (ref "R2") (pin "2") (pinfunction "2_2") (pintype "passive"))
      (node (ref "U$1") (pin "15") (pinfunction "DIO5_15") (pintype "bidirectional"))
    )
    (net (code "76") (name "unconnected-(CN1-PadID)") (class "Default")
      (node (ref "CN1") (pin "ID") (pinfunction "ID_ID") (pintype "bidirectional"))
    )
    (net (code "77") (name "unconnected-(IC6-GPB4-Pad5)") (class "Default")
      (node (ref "IC6") (pin "5") (pinfunction "GPB4_5") (pintype "bidirectional"))
    )
    (net (code "78") (name "unconnected-(IC6-GPB5-Pad6)") (class "Default")
      (node (ref "IC6") (pin "6") (pinfunction "GPB5_6") (pintype "bidirectional"))
    )
    (net (code "79") (name "unconnected-(IC6-GPB6-Pad7)") (class "Default")
      (node (ref "IC6") (pin "7") (pinfunction "GPB6_7") (pintype "bidirectional"))
    )
    (net (code "80") (name "unconnected-(IC6-GPB7-Pad8)") (class "Default")
      (node (ref "IC6") (pin "8") (pinfunction "GPB7_8") (pintype "bidirectional"))
    )
    (net (code "81") (name "unconnected-(IC6-INTA-Pad20)") (class "Default")
      (node (ref "IC6") (pin "20") (pinfunction "INTA_20") (pintype "output"))
    )
    (net (code "82") (name "unconnected-(IC6-INTB-Pad19)") (class "Default")
      (node (ref "IC6") (pin "19") (pinfunction "INTB_19") (pintype "output"))
    )
    (net (code "83") (name "unconnected-(IC8-PB0(SS)-Pad8)") (class "Default")
      (node (ref "IC8") (pin "8") (pinfunction "PB0(SS)_8") (pintype "bidirectional"))
    )
    (net (code "84") (name "unconnected-(IC8-PB4(ADC11)-Pad28)") (class "Default")
      (node (ref "IC8") (pin "28") (pinfunction "PB4(ADC11)_28") (pintype "bidirectional"))
    )
    (net (code "85") (name "unconnected-(IC8-PB5(OC1A{slash}ADC12{slash}~{OC4B})-Pad29)") (class "Default")
      (node (ref "IC8") (pin "29") (pinfunction "PB5(OC1A/ADC12/~{OC4B})_29") (pintype "bidirectional"))
    )
    (net (code "86") (name "unconnected-(IC8-PB6(OC1B{slash}OC4B{slash}ADC13)-Pad30)") (class "Default")
      (node (ref "IC8") (pin "30") (pinfunction "PB6(OC1B/OC4B/ADC13)_30") (pintype "bidirectional"))
    )
    (net (code "87") (name "unconnected-(IC8-PB7(OC0A{slash}OC1C{slash}RTS)-Pad12)") (class "Default")
      (node (ref "IC8") (pin "12") (pinfunction "PB7(OC0A/OC1C/RTS)_12") (pintype "bidirectional"))
    )
    (net (code "88") (name "unconnected-(IC8-PC6(OC3A{slash}~{OC4A})-Pad31)") (class "Default")
      (node (ref "IC8") (pin "31") (pinfunction "PC6(OC3A/~{OC4A})_31") (pintype "bidirectional"))
    )
    (net (code "89") (name "unconnected-(IC8-PC7(ICP3{slash}CLK0{slash}OC4A)-Pad32)") (class "Default")
      (node (ref "IC8") (pin "32") (pinfunction "PC7(ICP3/CLK0/OC4A)_32") (pintype "bidirectional"))
    )
    (net (code "90") (name "unconnected-(IC8-PD4(ICP1{slash}ADC8)-Pad25)") (class "Default")
      (node (ref "IC8") (pin "25") (pinfunction "PD4(ICP1/ADC8)_25") (pintype "bidirectional"))
    )
    (net (code "91") (name "unconnected-(IC8-PD5(XCK{slash}CTS)-Pad22)") (class "Default")
      (node (ref "IC8") (pin "22") (pinfunction "PD5(XCK/CTS)_22") (pintype "bidirectional"))
    )
    (net (code "92") (name "unconnected-(IC8-PD6(T1{slash}ADC9{slash}~{OC4D})-Pad26)") (class "Default")
      (node (ref "IC8") (pin "26") (pinfunction "PD6(T1/ADC9/~{OC4D})_26") (pintype "bidirectional"))
    )
    (net (code "93") (name "unconnected-(IC8-PD7(OC4D{slash}ADC10{slash}T0)-Pad27)") (class "Default")
      (node (ref "IC8") (pin "27") (pinfunction "PD7(OC4D/ADC10/T0)_27") (pintype "bidirectional"))
    )
    (net (code "94") (name "unconnected-(IC8-PE6(INT.6{slash}AIN0)-Pad1)") (class "Default")
      (node (ref "IC8") (pin "1") (pinfunction "PE6(INT.6/AIN0)_1") (pintype "bidirectional"))
    )
    (net (code "95") (name "unconnected-(IC8-PF0(ADC0)-Pad41)") (class "Default")
      (node (ref "IC8") (pin "41") (pinfunction "PF0(ADC0)_41") (pintype "bidirectional"))
    )
    (net (code "96") (name "unconnected-(IC8-PF1(ADC1)-Pad40)") (class "Default")
      (node (ref "IC8") (pin "40") (pinfunction "PF1(ADC1)_40") (pintype "bidirectional"))
    )
    (net (code "97") (name "unconnected-(IC8-PF4(ADC4{slash}TCK)-Pad39)") (class "Default")
      (node (ref "IC8") (pin "39") (pinfunction "PF4(ADC4/TCK)_39") (pintype "bidirectional"))
    )
    (net (code "98") (name "unconnected-(IC8-PF5(ADC5{slash}TMS)-Pad38)") (class "Default")
      (node (ref "IC8") (pin "38") (pinfunction "PF5(ADC5/TMS)_38") (pintype "bidirectional"))
    )
    (net (code "99") (name "unconnected-(IC8-PF6(ADC6{slash}TDO)-Pad37)") (class "Default")
      (node (ref "IC8") (pin "37") (pinfunction "PF6(ADC6/TDO)_37") (pintype "bidirectional"))
    )
    (net (code "100") (name "unconnected-(IC8-PF7(ADC7(TDI)-Pad36)") (class "Default")
      (node (ref "IC8") (pin "36") (pinfunction "PF7(ADC7(TDI)_36") (pintype "bidirectional"))
    )
    (net (code "101") (name "unconnected-(JK1-PadRSH)") (class "Default")
      (node (ref "JK1") (pin "RSH") (pinfunction "RSH_RSH") (pintype "bidirectional"))
    )
    (net (code "102") (name "unconnected-(JK2-PadRSH)") (class "Default")
      (node (ref "JK2") (pin "RSH") (pinfunction "RSH_RSH") (pintype "bidirectional"))
    )
    (net (code "103") (name "unconnected-(JK3-PadRSH)") (class "Default")
      (node (ref "JK3") (pin "RSH") (pinfunction "RSH_RSH") (pintype "bidirectional"))
    )
    (net (code "104") (name "unconnected-(JK4-PadRSH)") (class "Default")
      (node (ref "JK4") (pin "RSH") (pinfunction "RSH_RSH") (pintype "bidirectional"))
    )
    (net (code "105") (name "unconnected-(U$1-DIO0-Pad20)") (class "Default")
      (node (ref "U$1") (pin "20") (pinfunction "DIO0_20") (pintype "bidirectional"))
    )
    (net (code "106") (name "unconnected-(U$1-DIO1-Pad19)") (class "Default")
      (node (ref "U$1") (pin "19") (pinfunction "DIO1_19") (pintype "bidirectional"))
    )
    (net (code "107") (name "unconnected-(U$1-DIO2-Pad18)") (class "Default")
      (node (ref "U$1") (pin "18") (pinfunction "DIO2_18") (pintype "bidirectional"))
    )
    (net (code "108") (name "unconnected-(U$1-DIO3-Pad17)") (class "Default")
      (node (ref "U$1") (pin "17") (pinfunction "DIO3_17") (pintype "bidirectional"))
    )
    (net (code "109") (name "unconnected-(U$1-DIO4-Pad11)") (class "Default")
      (node (ref "U$1") (pin "11") (pinfunction "DIO4_11") (pintype "bidirectional"))
    )
    (net (code "110") (name "unconnected-(U$1-DIO9-Pad13)") (class "Default")
      (node (ref "U$1") (pin "13") (pinfunction "DIO9_13") (pintype "bidirectional"))
    )
    (net (code "111") (name "unconnected-(U$1-DIO11-Pad7)") (class "Default")
      (node (ref "U$1") (pin "7") (pinfunction "DIO11_7") (pintype "bidirectional"))
    )
    (net (code "112") (name "unconnected-(U$1-DIO12-Pad4)") (class "Default")
      (node (ref "U$1") (pin "4") (pinfunction "DIO12_4") (pintype "bidirectional"))
    )
    (net (code "113") (name "unconnected-(U$1-RES-Pad8)") (class "Default")
      (node (ref "U$1") (pin "8") (pinfunction "RES_8") (pintype "bidirectional"))
    )
    (net (code "114") (name "unconnected-(U$1-RES-Pad14)") (class "Default")
      (node (ref "U$1") (pin "14") (pinfunction "RES_14") (pintype "bidirectional"))
    )
  )
)
